# Hall_Effect_Sensors_Panel.net
KiCad netlist of a schematic drawn in Altium Designer
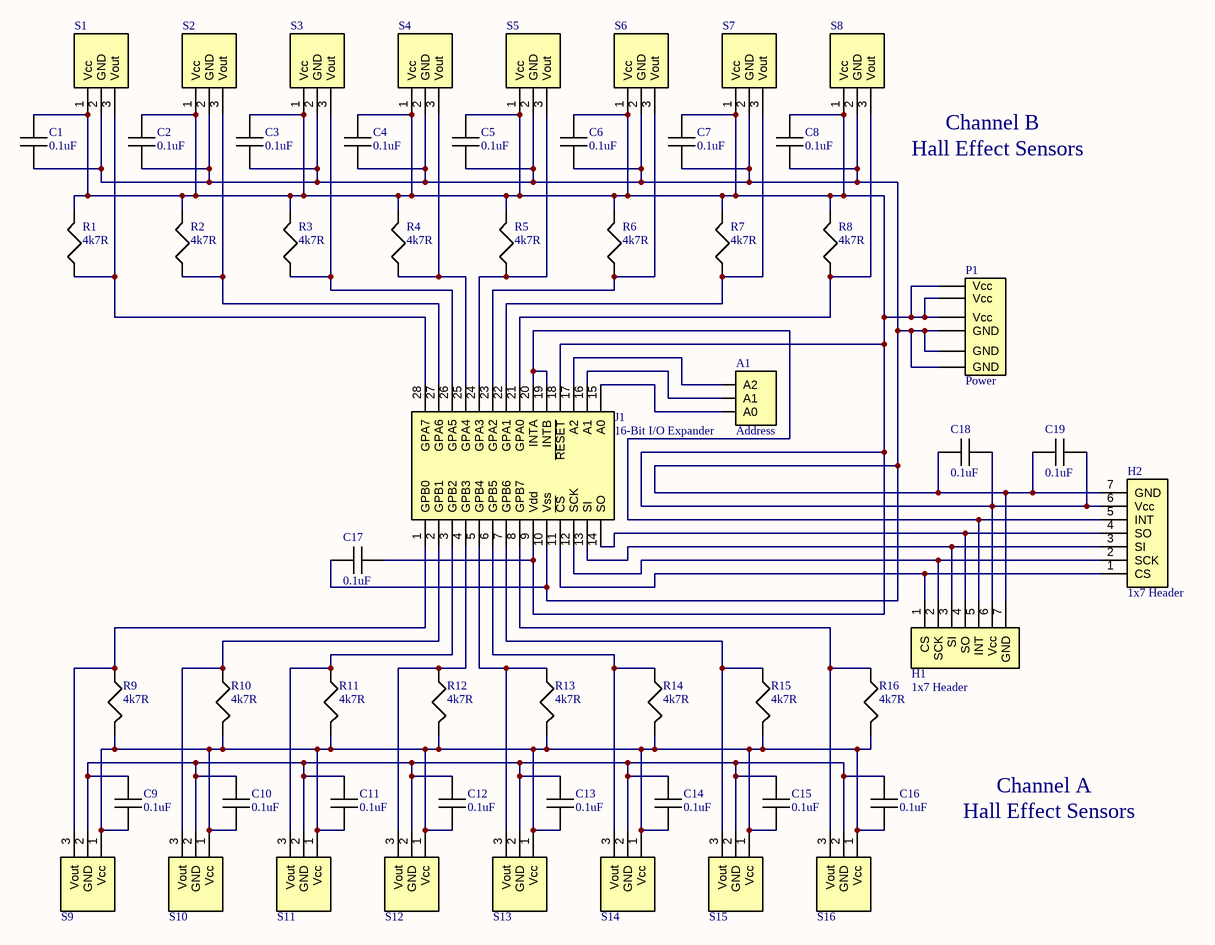
[diagram p0: Hall Effect Sensors Panel.SchDoc]

(export (version "E")
  (design (tool "Eeschema 10.0.6"))
  (components
    (comp (ref "A1")
      (value "Address")
      (footprint "Address")
      (libsource (lib "Hall Effect Sensor Panel Lib") (part "Address"))
    )
    (comp (ref "C1")
      (value "0.1uF")
      (footprint "C320C104K5R5TA")
      (fields
        (field (name "MANUFACTURER") "KEMET")
        (field (name "MANUFACTURER PART NUMBER") "C320C104K5R5TA")
        (field (name "TOLERANCE") "10%")
      )
      (libsource (lib "Hall Effect Sensor Panel Lib") (part "C320C104K5R5TA"))
    )
    (comp (ref "C2")
      (value "0.1uF")
      (footprint "C320C104K5R5TA")
      (fields
        (field (name "MANUFACTURER") "KEMET")
        (field (name "MANUFACTURER PART NUMBER") "C320C104K5R5TA")
        (field (name "TOLERANCE") "10%")
      )
      (libsource (lib "Hall Effect Sensor Panel Lib") (part "C320C104K5R5TA"))
    )
    (comp (ref "C3")
      (value "0.1uF")
      (footprint "C320C104K5R5TA")
      (fields
        (field (name "MANUFACTURER") "KEMET")
        (field (name "MANUFACTURER PART NUMBER") "C320C104K5R5TA")
        (field (name "TOLERANCE") "10%")
      )
      (libsource (lib "Hall Effect Sensor Panel Lib") (part "C320C104K5R5TA"))
    )
    (comp (ref "C4")
      (value "0.1uF")
      (footprint "C320C104K5R5TA")
      (fields
        (field (name "MANUFACTURER") "KEMET")
        (field (name "MANUFACTURER PART NUMBER") "C320C104K5R5TA")
        (field (name "TOLERANCE") "10%")
      )
      (libsource (lib "Hall Effect Sensor Panel Lib") (part "C320C104K5R5TA"))
    )
    (comp (ref "C5")
      (value "0.1uF")
      (footprint "C320C104K5R5TA")
      (fields
        (field (name "MANUFACTURER") "KEMET")
        (field (name "MANUFACTURER PART NUMBER") "C320C104K5R5TA")
        (field (name "TOLERANCE") "10%")
      )
      (libsource (lib "Hall Effect Sensor Panel Lib") (part "C320C104K5R5TA"))
    )
    (comp (ref "C6")
      (value "0.1uF")
      (footprint "C320C104K5R5TA")
      (fields
        (field (name "MANUFACTURER") "KEMET")
        (field (name "MANUFACTURER PART NUMBER") "C320C104K5R5TA")
        (field (name "TOLERANCE") "10%")
      )
      (libsource (lib "Hall Effect Sensor Panel Lib") (part "C320C104K5R5TA"))
    )
    (comp (ref "C7")
      (value "0.1uF")
      (footprint "C320C104K5R5TA")
      (fields
        (field (name "MANUFACTURER") "KEMET")
        (field (name "MANUFACTURER PART NUMBER") "C320C104K5R5TA")
        (field (name "TOLERANCE") "10%")
      )
      (libsource (lib "Hall Effect Sensor Panel Lib") (part "C320C104K5R5TA"))
    )
    (comp (ref "C8")
      (value "0.1uF")
      (footprint "C320C104K5R5TA")
      (fields
        (field (name "MANUFACTURER") "KEMET")
        (field (name "MANUFACTURER PART NUMBER") "C320C104K5R5TA")
        (field (name "TOLERANCE") "10%")
      )
      (libsource (lib "Hall Effect Sensor Panel Lib") (part "C320C104K5R5TA"))
    )
    (comp (ref "C9")
      (value "0.1uF")
      (footprint "C320C104K5R5TA")
      (fields
        (field (name "MANUFACTURER") "KEMET")
        (field (name "MANUFACTURER PART NUMBER") "C320C104K5R5TA")
        (field (name "TOLERANCE") "10%")
      )
      (libsource (lib "Hall Effect Sensor Panel Lib") (part "C320C104K5R5TA"))
    )
    (comp (ref "C10")
      (value "0.1uF")
      (footprint "C320C104K5R5TA")
      (fields
        (field (name "MANUFACTURER") "KEMET")
        (field (name "MANUFACTURER PART NUMBER") "C320C104K5R5TA")
        (field (name "TOLERANCE") "10%")
      )
      (libsource (lib "Hall Effect Sensor Panel Lib") (part "C320C104K5R5TA"))
    )
    (comp (ref "C11")
      (value "0.1uF")
      (footprint "C320C104K5R5TA")
      (fields
        (field (name "MANUFACTURER") "KEMET")
        (field (name "MANUFACTURER PART NUMBER") "C320C104K5R5TA")
        (field (name "TOLERANCE") "10%")
      )
      (libsource (lib "Hall Effect Sensor Panel Lib") (part "C320C104K5R5TA"))
    )
    (comp (ref "C12")
      (value "0.1uF")
      (footprint "C320C104K5R5TA")
      (fields
        (field (name "MANUFACTURER") "KEMET")
        (field (name "MANUFACTURER PART NUMBER") "C320C104K5R5TA")
        (field (name "TOLERANCE") "10%")
      )
      (libsource (lib "Hall Effect Sensor Panel Lib") (part "C320C104K5R5TA"))
    )
    (comp (ref "C13")
      (value "0.1uF")
      (footprint "C320C104K5R5TA")
      (fields
        (field (name "MANUFACTURER") "KEMET")
        (field (name "MANUFACTURER PART NUMBER") "C320C104K5R5TA")
        (field (name "TOLERANCE") "10%")
      )
      (libsource (lib "Hall Effect Sensor Panel Lib") (part "C320C104K5R5TA"))
    )
    (comp (ref "C14")
      (value "0.1uF")
      (footprint "C320C104K5R5TA")
      (fields
        (field (name "MANUFACTURER") "KEMET")
        (field (name "MANUFACTURER PART NUMBER") "C320C104K5R5TA")
        (field (name "TOLERANCE") "10%")
      )
      (libsource (lib "Hall Effect Sensor Panel Lib") (part "C320C104K5R5TA"))
    )
    (comp (ref "C15")
      (value "0.1uF")
      (footprint "C320C104K5R5TA")
      (fields
        (field (name "MANUFACTURER") "KEMET")
        (field (name "MANUFACTURER PART NUMBER") "C320C104K5R5TA")
        (field (name "TOLERANCE") "10%")
      )
      (libsource (lib "Hall Effect Sensor Panel Lib") (part "C320C104K5R5TA"))
    )
    (comp (ref "C16")
      (value "0.1uF")
      (footprint "C320C104K5R5TA")
      (fields
        (field (name "MANUFACTURER") "KEMET")
        (field (name "MANUFACTURER PART NUMBER") "C320C104K5R5TA")
        (field (name "TOLERANCE") "10%")
      )
      (libsource (lib "Hall Effect Sensor Panel Lib") (part "C320C104K5R5TA"))
    )
    (comp (ref "C17")
      (value "0.1uF")
      (footprint "C320C104K5R5TA")
      (fields
        (field (name "MANUFACTURER") "KEMET")
        (field (name "MANUFACTURER PART NUMBER") "C320C104K5R5TA")
        (field (name "TOLERANCE") "10%")
      )
      (libsource (lib "Hall Effect Sensor Panel Lib") (part "C320C104K5R5TA"))
    )
    (comp (ref "C18")
      (value "0.1uF")
      (footprint "C320C104K5R5TA")
      (fields
        (field (name "MANUFACTURER") "KEMET")
        (field (name "MANUFACTURER PART NUMBER") "C320C104K5R5TA")
        (field (name "TOLERANCE") "10%")
      )
      (libsource (lib "Hall Effect Sensor Panel Lib") (part "C320C104K5R5TA"))
    )
    (comp (ref "C19")
      (value "0.1uF")
      (footprint "C320C104K5R5TA")
      (fields
        (field (name "MANUFACTURER") "KEMET")
        (field (name "MANUFACTURER PART NUMBER") "C320C104K5R5TA")
        (field (name "TOLERANCE") "10%")
      )
      (libsource (lib "Hall Effect Sensor Panel Lib") (part "C320C104K5R5TA"))
    )
    (comp (ref "H1")
      (value "1x7 Header")
      (footprint "PCB Header")
      (description "CONN HEADER VERT 7POS 2.54MM")
      (fields (field (name "MANUFACTURER") "Molex") (field (name "MANUFACTURER PART NUMBER") "22-23-2071"))
      (libsource (lib "Hall Effect Sensor Panel Lib") (part "22-23-2071"))
    )
    (comp (ref "H2")
      (value "1x7 Header")
      (footprint "PCB Header")
      (description "CONN HEADER VERT 7POS 2.54MM")
      (fields (field (name "MANUFACTURER") "Molex") (field (name "MANUFACTURER PART NUMBER") "22-23-2071"))
      (libsource (lib "") (part "22-23-2071_1"))
    )
    (comp (ref "J1")
      (value "16-Bit I/O Expander")
      (footprint "MCP23S17-E/SP")
      (fields
        (field (name "MANUFACTURER") "Microchip")
        (field (name "MANUFACTURER PART NUMBER") "MCP23S17-E/SP")
        (field (name "TOLERANCE") "5%")
      )
      (libsource (lib "Hall Effect Sensor Panel Lib") (part "MCP23S17-E/SP"))
    )
    (comp (ref "P1")
      (value "Power")
      (footprint "Power")
      (libsource (lib "Hall Effect Sensor Panel Lib") (part "Power"))
    )
    (comp (ref "R1")
      (value "4k7R")
      (footprint "CFR100J4K7")
      (fields
        (field (name "MANUFACTURER") "TE Connectivity")
        (field (name "MANUFACTURER PART NUMBER") "CFR100J4K7")
        (field (name "TOLERANCE") "5%")
      )
      (libsource (lib "Hall Effect Sensor Panel Lib") (part "CFR100J4K7"))
    )
    (comp (ref "R2")
      (value "4k7R")
      (footprint "CFR100J4K7")
      (fields
        (field (name "MANUFACTURER") "TE Connectivity")
        (field (name "MANUFACTURER PART NUMBER") "CFR100J4K7")
        (field (name "TOLERANCE") "5%")
      )
      (libsource (lib "Hall Effect Sensor Panel Lib") (part "CFR100J4K7"))
    )
    (comp (ref "R3")
      (value "4k7R")
      (footprint "CFR100J4K7")
      (fields
        (field (name "MANUFACTURER") "TE Connectivity")
        (field (name "MANUFACTURER PART NUMBER") "CFR100J4K7")
        (field (name "TOLERANCE") "5%")
      )
      (libsource (lib "Hall Effect Sensor Panel Lib") (part "CFR100J4K7"))
    )
    (comp (ref "R4")
      (value "4k7R")
      (footprint "CFR100J4K7")
      (fields
        (field (name "MANUFACTURER") "TE Connectivity")
        (field (name "MANUFACTURER PART NUMBER") "CFR100J4K7")
        (field (name "TOLERANCE") "5%")
      )
      (libsource (lib "Hall Effect Sensor Panel Lib") (part "CFR100J4K7"))
    )
    (comp (ref "R5")
      (value "4k7R")
      (footprint "CFR100J4K7")
      (fields
        (field (name "MANUFACTURER") "TE Connectivity")
        (field (name "MANUFACTURER PART NUMBER") "CFR100J4K7")
        (field (name "TOLERANCE") "5%")
      )
      (libsource (lib "Hall Effect Sensor Panel Lib") (part "CFR100J4K7"))
    )
    (comp (ref "R6")
      (value "4k7R")
      (footprint "CFR100J4K7")
      (fields
        (field (name "MANUFACTURER") "TE Connectivity")
        (field (name "MANUFACTURER PART NUMBER") "CFR100J4K7")
        (field (name "TOLERANCE") "5%")
      )
      (libsource (lib "Hall Effect Sensor Panel Lib") (part "CFR100J4K7"))
    )
    (comp (ref "R7")
      (value "4k7R")
      (footprint "CFR100J4K7")
      (fields
        (field (name "MANUFACTURER") "TE Connectivity")
        (field (name "MANUFACTURER PART NUMBER") "CFR100J4K7")
        (field (name "TOLERANCE") "5%")
      )
      (libsource (lib "Hall Effect Sensor Panel Lib") (part "CFR100J4K7"))
    )
    (comp (ref "R8")
      (value "4k7R")
      (footprint "CFR100J4K7")
      (fields
        (field (name "MANUFACTURER") "TE Connectivity")
        (field (name "MANUFACTURER PART NUMBER") "CFR100J4K7")
        (field (name "TOLERANCE") "5%")
      )
      (libsource (lib "Hall Effect Sensor Panel Lib") (part "CFR100J4K7"))
    )
    (comp (ref "R9")
      (value "4k7R")
      (footprint "CFR100J4K7")
      (fields
        (field (name "MANUFACTURER") "TE Connectivity")
        (field (name "MANUFACTURER PART NUMBER") "CFR100J4K7")
        (field (name "TOLERANCE") "5%")
      )
      (libsource (lib "Hall Effect Sensor Panel Lib") (part "CFR100J4K7"))
    )
    (comp (ref "R10")
      (value "4k7R")
      (footprint "CFR100J4K7")
      (fields
        (field (name "MANUFACTURER") "TE Connectivity")
        (field (name "MANUFACTURER PART NUMBER") "CFR100J4K7")
        (field (name "TOLERANCE") "5%")
      )
      (libsource (lib "Hall Effect Sensor Panel Lib") (part "CFR100J4K7"))
    )
    (comp (ref "R11")
      (value "4k7R")
      (footprint "CFR100J4K7")
      (fields
        (field (name "MANUFACTURER") "TE Connectivity")
        (field (name "MANUFACTURER PART NUMBER") "CFR100J4K7")
        (field (name "TOLERANCE") "5%")
      )
      (libsource (lib "Hall Effect Sensor Panel Lib") (part "CFR100J4K7"))
    )
    (comp (ref "R12")
      (value "4k7R")
      (footprint "CFR100J4K7")
      (fields
        (field (name "MANUFACTURER") "TE Connectivity")
        (field (name "MANUFACTURER PART NUMBER") "CFR100J4K7")
        (field (name "TOLERANCE") "5%")
      )
      (libsource (lib "Hall Effect Sensor Panel Lib") (part "CFR100J4K7"))
    )
    (comp (ref "R13")
      (value "4k7R")
      (footprint "CFR100J4K7")
      (fields
        (field (name "MANUFACTURER") "TE Connectivity")
        (field (name "MANUFACTURER PART NUMBER") "CFR100J4K7")
        (field (name "TOLERANCE") "5%")
      )
      (libsource (lib "Hall Effect Sensor Panel Lib") (part "CFR100J4K7"))
    )
    (comp (ref "R14")
      (value "4k7R")
      (footprint "CFR100J4K7")
      (fields
        (field (name "MANUFACTURER") "TE Connectivity")
        (field (name "MANUFACTURER PART NUMBER") "CFR100J4K7")
        (field (name "TOLERANCE") "5%")
      )
      (libsource (lib "Hall Effect Sensor Panel Lib") (part "CFR100J4K7"))
    )
    (comp (ref "R15")
      (value "4k7R")
      (footprint "CFR100J4K7")
      (fields
        (field (name "MANUFACTURER") "TE Connectivity")
        (field (name "MANUFACTURER PART NUMBER") "CFR100J4K7")
        (field (name "TOLERANCE") "5%")
      )
      (libsource (lib "Hall Effect Sensor Panel Lib") (part "CFR100J4K7"))
    )
    (comp (ref "R16")
      (value "4k7R")
      (footprint "CFR100J4K7")
      (fields
        (field (name "MANUFACTURER") "TE Connectivity")
        (field (name "MANUFACTURER PART NUMBER") "CFR100J4K7")
        (field (name "TOLERANCE") "5%")
      )
      (libsource (lib "Hall Effect Sensor Panel Lib") (part "CFR100J4K7"))
    )
    (comp (ref "S1")
      (value "Hall Effect Sensor")
      (footprint "A1104EUA-T")
      (description "ALLEGRO MICROSYSTEMS - A1104EUA-T - IC, HALL-EFFECT SWITCH SIP-3")
      (fields
        (field (name "MANUFACTURER") "Allegro MicroSystems")
        (field (name "MANUFACTURER PART NUMBER") "A1104EUA-T")
      )
      (libsource (lib "") (part "A1104EUA-T_1"))
    )
    (comp (ref "S2")
      (value "Hall Effect Sensor")
      (footprint "A1104EUA-T")
      (description "ALLEGRO MICROSYSTEMS - A1104EUA-T - IC, HALL-EFFECT SWITCH SIP-3")
      (fields
        (field (name "MANUFACTURER") "Allegro MicroSystems")
        (field (name "MANUFACTURER PART NUMBER") "A1104EUA-T")
      )
      (libsource (lib "") (part "A1104EUA-T_1"))
    )
    (comp (ref "S3")
      (value "Hall Effect Sensor")
      (footprint "A1104EUA-T")
      (description "ALLEGRO MICROSYSTEMS - A1104EUA-T - IC, HALL-EFFECT SWITCH SIP-3")
      (fields
        (field (name "MANUFACTURER") "Allegro MicroSystems")
        (field (name "MANUFACTURER PART NUMBER") "A1104EUA-T")
      )
      (libsource (lib "") (part "A1104EUA-T_1"))
    )
    (comp (ref "S4")
      (value "Hall Effect Sensor")
      (footprint "A1104EUA-T")
      (description "ALLEGRO MICROSYSTEMS - A1104EUA-T - IC, HALL-EFFECT SWITCH SIP-3")
      (fields
        (field (name "MANUFACTURER") "Allegro MicroSystems")
        (field (name "MANUFACTURER PART NUMBER") "A1104EUA-T")
      )
      (libsource (lib "") (part "A1104EUA-T_1"))
    )
    (comp (ref "S5")
      (value "Hall Effect Sensor")
      (footprint "A1104EUA-T")
      (description "ALLEGRO MICROSYSTEMS - A1104EUA-T - IC, HALL-EFFECT SWITCH SIP-3")
      (fields
        (field (name "MANUFACTURER") "Allegro MicroSystems")
        (field (name "MANUFACTURER PART NUMBER") "A1104EUA-T")
      )
      (libsource (lib "") (part "A1104EUA-T_1"))
    )
    (comp (ref "S6")
      (value "Hall Effect Sensor")
      (footprint "A1104EUA-T")
      (description "ALLEGRO MICROSYSTEMS - A1104EUA-T - IC, HALL-EFFECT SWITCH SIP-3")
      (fields
        (field (name "MANUFACTURER") "Allegro MicroSystems")
        (field (name "MANUFACTURER PART NUMBER") "A1104EUA-T")
      )
      (libsource (lib "") (part "A1104EUA-T_1"))
    )
    (comp (ref "S7")
      (value "Hall Effect Sensor")
      (footprint "A1104EUA-T")
      (description "ALLEGRO MICROSYSTEMS - A1104EUA-T - IC, HALL-EFFECT SWITCH SIP-3")
      (fields
        (field (name "MANUFACTURER") "Allegro MicroSystems")
        (field (name "MANUFACTURER PART NUMBER") "A1104EUA-T")
      )
      (libsource (lib "") (part "A1104EUA-T_1"))
    )
    (comp (ref "S8")
      (value "Hall Effect Sensor")
      (footprint "A1104EUA-T")
      (description "ALLEGRO MICROSYSTEMS - A1104EUA-T - IC, HALL-EFFECT SWITCH SIP-3")
      (fields
        (field (name "MANUFACTURER") "Allegro MicroSystems")
        (field (name "MANUFACTURER PART NUMBER") "A1104EUA-T")
      )
      (libsource (lib "") (part "A1104EUA-T_1"))
    )
    (comp (ref "S9")
      (value "Hall Effect Sensor")
      (footprint "A1104EUA-T")
      (description "ALLEGRO MICROSYSTEMS - A1104EUA-T - IC, HALL-EFFECT SWITCH SIP-3")
      (fields
        (field (name "MANUFACTURER") "Allegro MicroSystems")
        (field (name "MANUFACTURER PART NUMBER") "A1104EUA-T")
      )
      (libsource (lib "Hall Effect Sensor Panel Lib") (part "A1104EUA-T"))
    )
    (comp (ref "S10")
      (value "Hall Effect Sensor")
      (footprint "A1104EUA-T")
      (description "ALLEGRO MICROSYSTEMS - A1104EUA-T - IC, HALL-EFFECT SWITCH SIP-3")
      (fields
        (field (name "MANUFACTURER") "Allegro MicroSystems")
        (field (name "MANUFACTURER PART NUMBER") "A1104EUA-T")
      )
      (libsource (lib "Hall Effect Sensor Panel Lib") (part "A1104EUA-T"))
    )
    (comp (ref "S11")
      (value "Hall Effect Sensor")
      (footprint "A1104EUA-T")
      (description "ALLEGRO MICROSYSTEMS - A1104EUA-T - IC, HALL-EFFECT SWITCH SIP-3")
      (fields
        (field (name "MANUFACTURER") "Allegro MicroSystems")
        (field (name "MANUFACTURER PART NUMBER") "A1104EUA-T")
      )
      (libsource (lib "Hall Effect Sensor Panel Lib") (part "A1104EUA-T"))
    )
    (comp (ref "S12")
      (value "Hall Effect Sensor")
      (footprint "A1104EUA-T")
      (description "ALLEGRO MICROSYSTEMS - A1104EUA-T - IC, HALL-EFFECT SWITCH SIP-3")
      (fields
        (field (name "MANUFACTURER") "Allegro MicroSystems")
        (field (name "MANUFACTURER PART NUMBER") "A1104EUA-T")
      )
      (libsource (lib "Hall Effect Sensor Panel Lib") (part "A1104EUA-T"))
    )
    (comp (ref "S13")
      (value "Hall Effect Sensor")
      (footprint "A1104EUA-T")
      (description "ALLEGRO MICROSYSTEMS - A1104EUA-T - IC, HALL-EFFECT SWITCH SIP-3")
      (fields
        (field (name "MANUFACTURER") "Allegro MicroSystems")
        (field (name "MANUFACTURER PART NUMBER") "A1104EUA-T")
      )
      (libsource (lib "Hall Effect Sensor Panel Lib") (part "A1104EUA-T"))
    )
    (comp (ref "S14")
      (value "Hall Effect Sensor")
      (footprint "A1104EUA-T")
      (description "ALLEGRO MICROSYSTEMS - A1104EUA-T - IC, HALL-EFFECT SWITCH SIP-3")
      (fields
        (field (name "MANUFACTURER") "Allegro MicroSystems")
        (field (name "MANUFACTURER PART NUMBER") "A1104EUA-T")
      )
      (libsource (lib "Hall Effect Sensor Panel Lib") (part "A1104EUA-T"))
    )
    (comp (ref "S15")
      (value "Hall Effect Sensor")
      (footprint "A1104EUA-T")
      (description "ALLEGRO MICROSYSTEMS - A1104EUA-T - IC, HALL-EFFECT SWITCH SIP-3")
      (fields
        (field (name "MANUFACTURER") "Allegro MicroSystems")
        (field (name "MANUFACTURER PART NUMBER") "A1104EUA-T")
      )
      (libsource (lib "Hall Effect Sensor Panel Lib") (part "A1104EUA-T"))
    )
    (comp (ref "S16")
      (value "Hall Effect Sensor")
      (footprint "A1104EUA-T")
      (description "ALLEGRO MICROSYSTEMS - A1104EUA-T - IC, HALL-EFFECT SWITCH SIP-3")
      (fields
        (field (name "MANUFACTURER") "Allegro MicroSystems")
        (field (name "MANUFACTURER PART NUMBER") "A1104EUA-T")
      )
      (libsource (lib "Hall Effect Sensor Panel Lib") (part "A1104EUA-T"))
    )
  )
  (nets
    (net (code "1") (name "Net-(A1-A0)") (class "Default")
      (node (ref "A1") (pin "1") (pinfunction "A0_1") (pintype "passive"))
      (node (ref "J1") (pin "15") (pinfunction "A0_15") (pintype "passive"))
    )
    (net (code "2") (name "Net-(A1-A1)") (class "Default")
      (node (ref "A1") (pin "2") (pinfunction "A1_2") (pintype "passive"))
      (node (ref "J1") (pin "16") (pinfunction "A1_16") (pintype "passive"))
    )
    (net (code "3") (name "Net-(A1-A2)") (class "Default")
      (node (ref "A1") (pin "3") (pinfunction "A2_3") (pintype "passive"))
      (node (ref "J1") (pin "17") (pinfunction "A2_17") (pintype "passive"))
    )
    (net (code "4") (name "Net-(C1-48)") (class "Default")
      (node (ref "C1") (pin "1") (pinfunction "48_1") (pintype "passive"))
      (node (ref "C17") (pin "2") (pinfunction "2_2") (pintype "passive"))
      (node (ref "C18") (pin "2") (pinfunction "2_2") (pintype "passive"))
      (node (ref "C19") (pin "2") (pinfunction "2_2") (pintype "passive"))
      (node (ref "C2") (pin "1") (pinfunction "48_1") (pintype "passive"))
      (node (ref "C3") (pin "1") (pinfunction "48_1") (pintype "passive"))
      (node (ref "C4") (pin "1") (pinfunction "48_1") (pintype "passive"))
      (node (ref "C5") (pin "1") (pinfunction "48_1") (pintype "passive"))
      (node (ref "C6") (pin "1") (pinfunction "48_1") (pintype "passive"))
      (node (ref "C7") (pin "1") (pinfunction "48_1") (pintype "passive"))
      (node (ref "C8") (pin "1") (pinfunction "48_1") (pintype "passive"))
      (node (ref "H1") (pin "6") (pinfunction "Vcc_6") (pintype "passive"))
      (node (ref "H2") (pin "6") (pinfunction "Vcc_6") (pintype "passive"))
      (node (ref "J1") (pin "18") (pinfunction "~{RESET}_18") (pintype "passive"))
      (node (ref "J1") (pin "9") (pinfunction "Vdd_9") (pintype "passive"))
      (node (ref "P1") (pin "1") (pinfunction "Vcc_1") (pintype "passive"))
      (node (ref "P1") (pin "2") (pinfunction "Vcc_2") (pintype "passive"))
      (node (ref "P1") (pin "3") (pinfunction "Vcc_3") (pintype "passive"))
      (node (ref "R1") (pin "2") (pinfunction "2_2") (pintype "passive"))
      (node (ref "R2") (pin "2") (pinfunction "2_2") (pintype "passive"))
      (node (ref "R3") (pin "2") (pinfunction "2_2") (pintype "passive"))
      (node (ref "R4") (pin "2") (pinfunction "2_2") (pintype "passive"))
      (node (ref "R5") (pin "2") (pinfunction "2_2") (pintype "passive"))
      (node (ref "R6") (pin "2") (pinfunction "2_2") (pintype "passive"))
      (node (ref "R7") (pin "2") (pinfunction "2_2") (pintype "passive"))
      (node (ref "R8") (pin "2") (pinfunction "2_2") (pintype "passive"))
      (node (ref "S1") (pin "1") (pinfunction "Vcc_1") (pintype "passive"))
      (node (ref "S2") (pin "1") (pinfunction "Vcc_1") (pintype "passive"))
      (node (ref "S3") (pin "1") (pinfunction "Vcc_1") (pintype "passive"))
      (node (ref "S4") (pin "1") (pinfunction "Vcc_1") (pintype "passive"))
      (node (ref "S5") (pin "1") (pinfunction "Vcc_1") (pintype "passive"))
      (node (ref "S6") (pin "1") (pinfunction "Vcc_1") (pintype "passive"))
      (node (ref "S7") (pin "1") (pinfunction "Vcc_1") (pintype "passive"))
      (node (ref "S8") (pin "1") (pinfunction "Vcc_1") (pintype "passive"))
    )
    (net (code "5") (name "Net-(C10-48)") (class "Default")
      (node (ref "C10") (pin "1") (pinfunction "48_1") (pintype "passive"))
      (node (ref "C11") (pin "1") (pinfunction "48_1") (pintype "passive"))
      (node (ref "C12") (pin "1") (pinfunction "48_1") (pintype "passive"))
      (node (ref "C13") (pin "1") (pinfunction "48_1") (pintype "passive"))
      (node (ref "C14") (pin "1") (pinfunction "48_1") (pintype "passive"))
      (node (ref "C15") (pin "1") (pinfunction "48_1") (pintype "passive"))
      (node (ref "C16") (pin "1") (pinfunction "48_1") (pintype "passive"))
      (node (ref "C9") (pin "1") (pinfunction "48_1") (pintype "passive"))
      (node (ref "R10") (pin "2") (pinfunction "2_2") (pintype "passive"))
      (node (ref "R11") (pin "2") (pinfunction "2_2") (pintype "passive"))
      (node (ref "R12") (pin "2") (pinfunction "2_2") (pintype "passive"))
      (node (ref "R13") (pin "2") (pinfunction "2_2") (pintype "passive"))
      (node (ref "R14") (pin "2") (pinfunction "2_2") (pintype "passive"))
      (node (ref "R15") (pin "2") (pinfunction "2_2") (pintype "passive"))
      (node (ref "R16") (pin "2") (pinfunction "2_2") (pintype "passive"))
      (node (ref "R9") (pin "2") (pinfunction "2_2") (pintype "passive"))
      (node (ref "S10") (pin "1") (pinfunction "Vcc_1") (pintype "passive"))
      (node (ref "S11") (pin "1") (pinfunction "Vcc_1") (pintype "passive"))
      (node (ref "S12") (pin "1") (pinfunction "Vcc_1") (pintype "passive"))
      (node (ref "S13") (pin "1") (pinfunction "Vcc_1") (pintype "passive"))
      (node (ref "S14") (pin "1") (pinfunction "Vcc_1") (pintype "passive"))
      (node (ref "S15") (pin "1") (pinfunction "Vcc_1") (pintype "passive"))
      (node (ref "S16") (pin "1") (pinfunction "Vcc_1") (pintype "passive"))
      (node (ref "S9") (pin "1") (pinfunction "Vcc_1") (pintype "passive"))
    )
    (net (code "6") (name "Net-(C17-48)") (class "Default")
      (node (ref "C1") (pin "2") (pinfunction "2_2") (pintype "passive"))
      (node (ref "C17") (pin "1") (pinfunction "48_1") (pintype "passive"))
      (node (ref "C18") (pin "1") (pinfunction "48_1") (pintype "passive"))
      (node (ref "C19") (pin "1") (pinfunction "48_1") (pintype "passive"))
      (node (ref "C2") (pin "2") (pinfunction "2_2") (pintype "passive"))
      (node (ref "C3") (pin "2") (pinfunction "2_2") (pintype "passive"))
      (node (ref "C4") (pin "2") (pinfunction "2_2") (pintype "passive"))
      (node (ref "C5") (pin "2") (pinfunction "2_2") (pintype "passive"))
      (node (ref "C6") (pin "2") (pinfunction "2_2") (pintype "passive"))
      (node (ref "C7") (pin "2") (pinfunction "2_2") (pintype "passive"))
      (node (ref "C8") (pin "2") (pinfunction "2_2") (pintype "passive"))
      (node (ref "H1") (pin "7") (pinfunction "GND_7") (pintype "passive"))
      (node (ref "H2") (pin "7") (pinfunction "GND_7") (pintype "passive"))
      (node (ref "J1") (pin "10") (pinfunction "Vss_10") (pintype "passive"))
      (node (ref "P1") (pin "4") (pinfunction "GND_4") (pintype "passive"))
      (node (ref "P1") (pin "5") (pinfunction "GND_5") (pintype "passive"))
      (node (ref "P1") (pin "6") (pinfunction "GND_6") (pintype "passive"))
      (node (ref "S1") (pin "2") (pinfunction "GND_2") (pintype "passive"))
      (node (ref "S2") (pin "2") (pinfunction "GND_2") (pintype "passive"))
      (node (ref "S3") (pin "2") (pinfunction "GND_2") (pintype "passive"))
      (node (ref "S4") (pin "2") (pinfunction "GND_2") (pintype "passive"))
      (node (ref "S5") (pin "2") (pinfunction "GND_2") (pintype "passive"))
      (node (ref "S6") (pin "2") (pinfunction "GND_2") (pintype "passive"))
      (node (ref "S7") (pin "2") (pinfunction "GND_2") (pintype "passive"))
      (node (ref "S8") (pin "2") (pinfunction "GND_2") (pintype "passive"))
    )
    (net (code "7") (name "Net-(H1-CS)") (class "Default")
      (node (ref "H1") (pin "1") (pinfunction "CS_1") (pintype "passive"))
      (node (ref "H2") (pin "1") (pinfunction "CS_1") (pintype "passive"))
      (node (ref "J1") (pin "11") (pinfunction "~{CS}_11") (pintype "passive"))
    )
    (net (code "8") (name "Net-(H1-INT)") (class "Default")
      (node (ref "H1") (pin "5") (pinfunction "INT_5") (pintype "passive"))
      (node (ref "H2") (pin "5") (pinfunction "INT_5") (pintype "passive"))
      (node (ref "J1") (pin "19") (pinfunction "INTB_19") (pintype "passive"))
      (node (ref "J1") (pin "20") (pinfunction "INTA_20") (pintype "passive"))
    )
    (net (code "9") (name "Net-(H1-SCK)") (class "Default")
      (node (ref "H1") (pin "2") (pinfunction "SCK_2") (pintype "passive"))
      (node (ref "H2") (pin "2") (pinfunction "SCK_2") (pintype "passive"))
      (node (ref "J1") (pin "12") (pinfunction "SCK_12") (pintype "passive"))
    )
    (net (code "10") (name "Net-(H1-SI)") (class "Default")
      (node (ref "H1") (pin "3") (pinfunction "SI_3") (pintype "passive"))
      (node (ref "H2") (pin "3") (pinfunction "SI_3") (pintype "passive"))
      (node (ref "J1") (pin "13") (pinfunction "SI_13") (pintype "passive"))
    )
    (net (code "11") (name "Net-(H1-SO)") (class "Default")
      (node (ref "H1") (pin "4") (pinfunction "SO_4") (pintype "passive"))
      (node (ref "H2") (pin "4") (pinfunction "SO_4") (pintype "passive"))
      (node (ref "J1") (pin "14") (pinfunction "SO_14") (pintype "passive"))
    )
    (net (code "12") (name "Net-(J1-GPA0)") (class "Default")
      (node (ref "J1") (pin "21") (pinfunction "GPA0_21") (pintype "passive"))
      (node (ref "R8") (pin "1") (pinfunction "1_1") (pintype "passive"))
      (node (ref "S8") (pin "3") (pinfunction "Vout_3") (pintype "passive"))
    )
    (net (code "13") (name "Net-(J1-GPA1)") (class "Default")
      (node (ref "J1") (pin "22") (pinfunction "GPA1_22") (pintype "passive"))
      (node (ref "R7") (pin "1") (pinfunction "1_1") (pintype "passive"))
      (node (ref "S7") (pin "3") (pinfunction "Vout_3") (pintype "passive"))
    )
    (net (code "14") (name "Net-(J1-GPA2)") (class "Default")
      (node (ref "J1") (pin "23") (pinfunction "GPA2_23") (pintype "passive"))
      (node (ref "R6") (pin "1") (pinfunction "1_1") (pintype "passive"))
      (node (ref "S6") (pin "3") (pinfunction "Vout_3") (pintype "passive"))
    )
    (net (code "15") (name "Net-(J1-GPA3)") (class "Default")
      (node (ref "J1") (pin "24") (pinfunction "GPA3_24") (pintype "passive"))
      (node (ref "R5") (pin "1") (pinfunction "1_1") (pintype "passive"))
      (node (ref "S5") (pin "3") (pinfunction "Vout_3") (pintype "passive"))
    )
    (net (code "16") (name "Net-(J1-GPA4)") (class "Default")
      (node (ref "J1") (pin "25") (pinfunction "GPA4_25") (pintype "passive"))
      (node (ref "R4") (pin "1") (pinfunction "1_1") (pintype "passive"))
      (node (ref "S4") (pin "3") (pinfunction "Vout_3") (pintype "passive"))
    )
    (net (code "17") (name "Net-(J1-GPA5)") (class "Default")
      (node (ref "J1") (pin "26") (pinfunction "GPA5_26") (pintype "passive"))
      (node (ref "R3") (pin "1") (pinfunction "1_1") (pintype "passive"))
      (node (ref "S3") (pin "3") (pinfunction "Vout_3") (pintype "passive"))
    )
    (net (code "18") (name "Net-(J1-GPA6)") (class "Default")
      (node (ref "J1") (pin "27") (pinfunction "GPA6_27") (pintype "passive"))
      (node (ref "R2") (pin "1") (pinfunction "1_1") (pintype "passive"))
      (node (ref "S2") (pin "3") (pinfunction "Vout_3") (pintype "passive"))
    )
    (net (code "19") (name "Net-(J1-GPA7)") (class "Default")
      (node (ref "J1") (pin "28") (pinfunction "GPA7_28") (pintype "passive"))
      (node (ref "R1") (pin "1") (pinfunction "1_1") (pintype "passive"))
      (node (ref "S1") (pin "3") (pinfunction "Vout_3") (pintype "passive"))
    )
    (net (code "20") (name "Net-(J1-GPB0)") (class "Default")
      (node (ref "J1") (pin "1") (pinfunction "GPB0_1") (pintype "passive"))
      (node (ref "R9") (pin "1") (pinfunction "1_1") (pintype "passive"))
      (node (ref "S9") (pin "3") (pinfunction "Vout_3") (pintype "passive"))
    )
    (net (code "21") (name "Net-(J1-GPB1)") (class "Default")
      (node (ref "J1") (pin "2") (pinfunction "GPB1_2") (pintype "passive"))
      (node (ref "R10") (pin "1") (pinfunction "1_1") (pintype "passive"))
      (node (ref "S10") (pin "3") (pinfunction "Vout_3") (pintype "passive"))
    )
    (net (code "22") (name "Net-(J1-GPB2)") (class "Default")
      (node (ref "J1") (pin "3") (pinfunction "GPB2_3") (pintype "passive"))
      (node (ref "R11") (pin "1") (pinfunction "1_1") (pintype "passive"))
      (node (ref "S11") (pin "3") (pinfunction "Vout_3") (pintype "passive"))
    )
    (net (code "23") (name "Net-(J1-GPB3)") (class "Default")
      (node (ref "J1") (pin "4") (pinfunction "GPB3_4") (pintype "passive"))
      (node (ref "R12") (pin "1") (pinfunction "1_1") (pintype "passive"))
      (node (ref "S12") (pin "3") (pinfunction "Vout_3") (pintype "passive"))
    )
    (net (code "24") (name "Net-(J1-GPB4)") (class "Default")
      (node (ref "J1") (pin "5") (pinfunction "GPB4_5") (pintype "passive"))
      (node (ref "R13") (pin "1") (pinfunction "1_1") (pintype "passive"))
      (node (ref "S13") (pin "3") (pinfunction "Vout_3") (pintype "passive"))
    )
    (net (code "25") (name "Net-(J1-GPB5)") (class "Default")
      (node (ref "J1") (pin "6") (pinfunction "GPB5_6") (pintype "passive"))
      (node (ref "R14") (pin "1") (pinfunction "1_1") (pintype "passive"))
      (node (ref "S14") (pin "3") (pinfunction "Vout_3") (pintype "passive"))
    )
    (net (code "26") (name "Net-(J1-GPB6)") (class "Default")
      (node (ref "J1") (pin "7") (pinfunction "GPB6_7") (pintype "passive"))
      (node (ref "R15") (pin "1") (pinfunction "1_1") (pintype "passive"))
      (node (ref "S15") (pin "3") (pinfunction "Vout_3") (pintype "passive"))
    )
    (net (code "27") (name "Net-(J1-GPB7)") (class "Default")
      (node (ref "J1") (pin "8") (pinfunction "GPB7_8") (pintype "passive"))
      (node (ref "R16") (pin "1") (pinfunction "1_1") (pintype "passive"))
      (node (ref "S16") (pin "3") (pinfunction "Vout_3") (pintype "passive"))
    )
    (net (code "28") (name "Net-(S10-GND)") (class "Default")
      (node (ref "C10") (pin "2") (pinfunction "2_2") (pintype "passive"))
      (node (ref "C11") (pin "2") (pinfunction "2_2") (pintype "passive"))
      (node (ref "C12") (pin "2") (pinfunction "2_2") (pintype "passive"))
      (node (ref "C13") (pin "2") (pinfunction "2_2") (pintype "passive"))
      (node (ref "C14") (pin "2") (pinfunction "2_2") (pintype "passive"))
      (node (ref "C15") (pin "2") (pinfunction "2_2") (pintype "passive"))
      (node (ref "C16") (pin "2") (pinfunction "2_2") (pintype "passive"))
      (node (ref "C9") (pin "2") (pinfunction "2_2") (pintype "passive"))
      (node (ref "S10") (pin "2") (pinfunction "GND_2") (pintype "passive"))
      (node (ref "S11") (pin "2") (pinfunction "GND_2") (pintype "passive"))
      (node (ref "S12") (pin "2") (pinfunction "GND_2") (pintype "passive"))
      (node (ref "S13") (pin "2") (pinfunction "GND_2") (pintype "passive"))
      (node (ref "S14") (pin "2") (pinfunction "GND_2") (pintype "passive"))
      (node (ref "S15") (pin "2") (pinfunction "GND_2") (pintype "passive"))
      (node (ref "S16") (pin "2") (pinfunction "GND_2") (pintype "passive"))
      (node (ref "S9") (pin "2") (pinfunction "GND_2") (pintype "passive"))
    )
  )
)
